# UWB_Conectores.net
KiCad netlist of a schematic drawn in Altium Designer
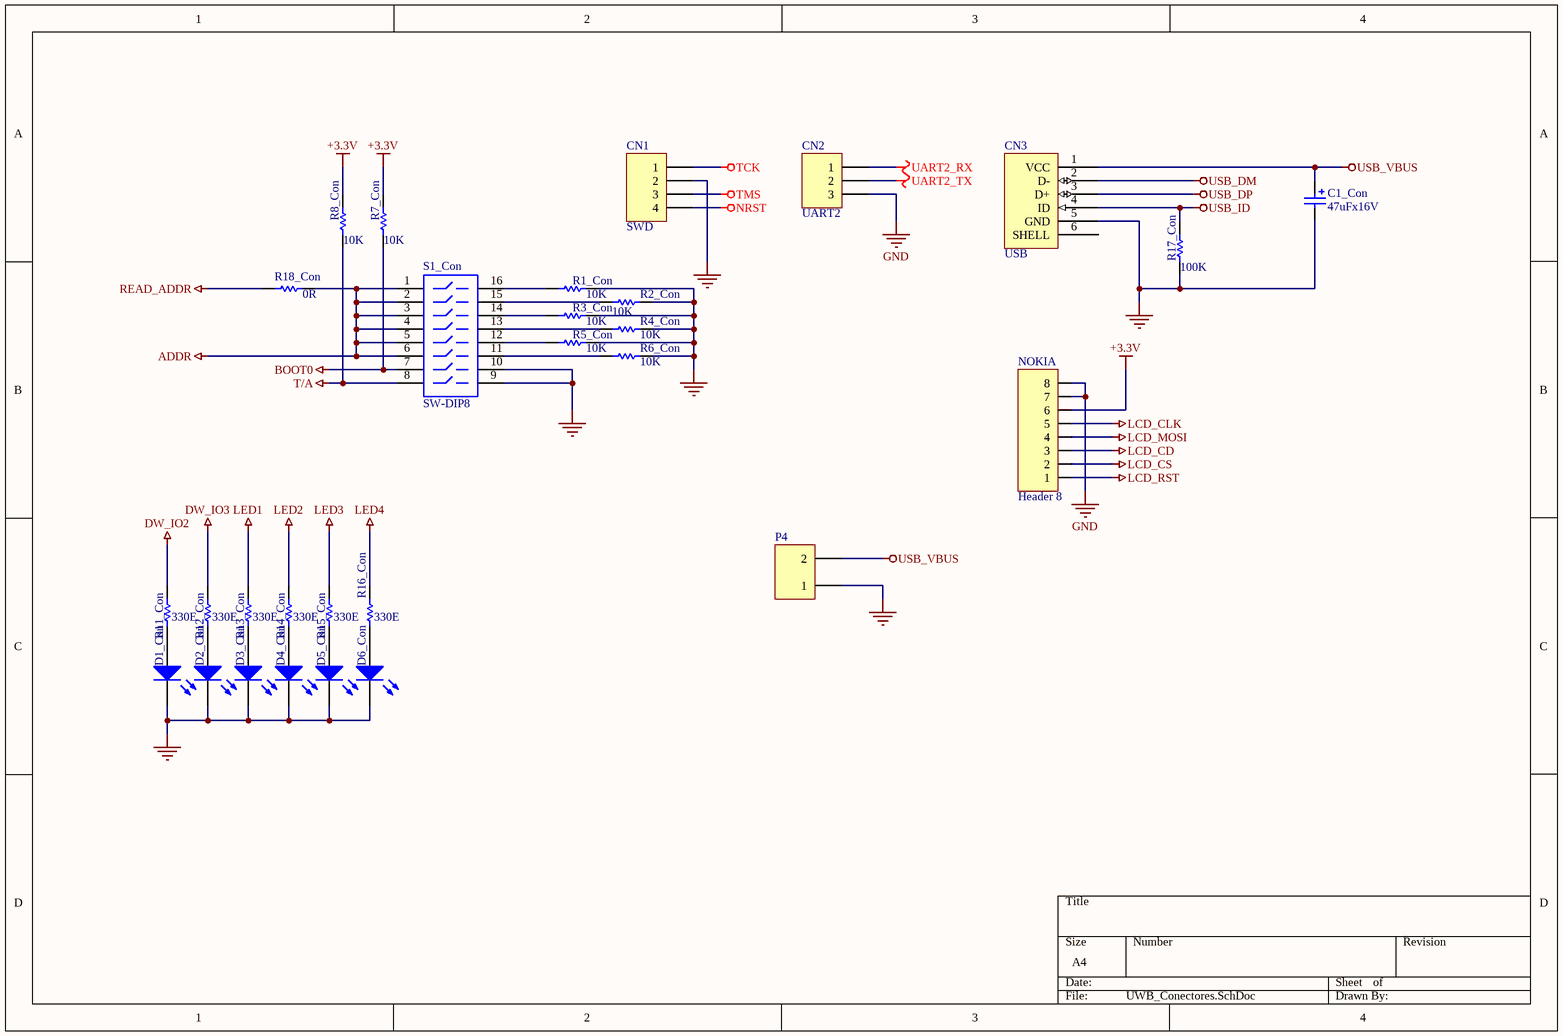
[diagram p0: UWB_Conectores.SchDoc]

(export (version "E")
  (design (tool "Eeschema 10.0.6"))
  (components
    (comp (ref "C1_Con")
      (value "47uFx16V")
      (footprint "Panasonic Size D (Dia. 6.3)")
      (description "Polarized Capacitor (Radial)")
      (fields (field (name "Comment") "Cap Pol1") (field (name "PUBLISHER") "Altium Limited"))
      (libsource (lib "Leo") (part "Cap Pol1"))
    )
    (comp (ref "CN1")
      (value "SWD")
      (footprint "Lib 01:HDR1X4 - SMALL")
      (description "Header, 4-Pin")
      (fields (field (name "PUBLISHER") "Altium Limited"))
      (libsource (lib "Miscellaneous Connectors") (part "Header 4"))
    )
    (comp (ref "CN2")
      (value "UART2")
      (footprint "HDR1X3")
      (description "Header, 3-Pin")
      (fields (field (name "PUBLISHER") "Altium Limited"))
      (libsource (lib "Miscellaneous Connectors") (part "Header 3"))
    )
    (comp (ref "CN3")
      (value "USB")
      (footprint "USB_Montaje")
      (description "USB-MINI-typeB connector")
      (libsource (lib "MCD_TOOLS") (part "USB-MINI-typeB connector"))
    )
    (comp (ref "D1_Con")
      (value "LED")
      (footprint "LED SMD 0805")
      (description "Typical INFRARED GaAs LED")
      (fields (field (name "PUBLISHER") "Altium Limited"))
      (libsource (lib "Leo") (part "LED"))
    )
    (comp (ref "D2_Con")
      (value "LED")
      (footprint "LED SMD 0805")
      (description "Typical INFRARED GaAs LED")
      (fields (field (name "PUBLISHER") "Altium Limited"))
      (libsource (lib "Leo") (part "LED"))
    )
    (comp (ref "D3_Con")
      (value "LED")
      (footprint "LED SMD 0805")
      (description "Typical INFRARED GaAs LED")
      (fields (field (name "PUBLISHER") "Altium Limited"))
      (libsource (lib "Leo") (part "LED"))
    )
    (comp (ref "D4_Con")
      (value "LED")
      (footprint "LED SMD 0805")
      (description "Typical INFRARED GaAs LED")
      (fields (field (name "PUBLISHER") "Altium Limited"))
      (libsource (lib "Leo") (part "LED"))
    )
    (comp (ref "D5_Con")
      (value "LED")
      (footprint "LED SMD 0805")
      (description "Typical INFRARED GaAs LED")
      (fields (field (name "PUBLISHER") "Altium Limited"))
      (libsource (lib "Leo") (part "LED"))
    )
    (comp (ref "D6_Con")
      (value "LED")
      (footprint "LED SMD 0805")
      (description "Typical INFRARED GaAs LED")
      (fields (field (name "PUBLISHER") "Altium Limited"))
      (libsource (lib "Leo") (part "LED"))
    )
    (comp (ref "NOKIA") (value "Header 8") (footprint "HDR1X8") (libsource (lib "Leo") (part "Header 8")))
    (comp (ref "P4")
      (value "Header 2")
      (footprint "HDR1X2")
      (description "Header, 2-Pin")
      (fields (field (name "PUBLISHER") "Altium Limited"))
      (libsource (lib "Leo") (part "Header 2"))
    )
    (comp (ref "R1_Con")
      (value "10K")
      (footprint "Chip_Resistor_M:RESC1608M")
      (description "Resistor")
      (fields (field (name "PUBLISHER") "Altium Limited"))
      (libsource (lib "Miscellaneous Devices") (part "res1"))
    )
    (comp (ref "R2_Con")
      (value "10K")
      (footprint "Chip_Resistor_M:RESC1608M")
      (description "Resistor")
      (fields (field (name "PUBLISHER") "Altium Limited"))
      (libsource (lib "Miscellaneous Devices") (part "res1"))
    )
    (comp (ref "R3_Con")
      (value "10K")
      (footprint "Chip_Resistor_M:RESC1608M")
      (description "Resistor")
      (fields (field (name "PUBLISHER") "Altium Limited"))
      (libsource (lib "Miscellaneous Devices") (part "res1"))
    )
    (comp (ref "R4_Con")
      (value "10K")
      (footprint "Chip_Resistor_M:RESC1608M")
      (description "Resistor")
      (fields (field (name "PUBLISHER") "Altium Limited"))
      (libsource (lib "Miscellaneous Devices") (part "res1"))
    )
    (comp (ref "R5_Con")
      (value "10K")
      (footprint "Chip_Resistor_M:RESC1608M")
      (description "Resistor")
      (fields (field (name "PUBLISHER") "Altium Limited"))
      (libsource (lib "Miscellaneous Devices") (part "res1"))
    )
    (comp (ref "R6_Con")
      (value "10K")
      (footprint "Chip_Resistor_M:RESC1608M")
      (description "Resistor")
      (fields (field (name "PUBLISHER") "Altium Limited"))
      (libsource (lib "Miscellaneous Devices") (part "res1"))
    )
    (comp (ref "R7_Con")
      (value "10K")
      (footprint "Chip_Resistor_M:RESC1608M")
      (description "Resistor")
      (fields (field (name "PUBLISHER") "Altium Limited"))
      (libsource (lib "Miscellaneous Devices") (part "res1"))
    )
    (comp (ref "R8_Con")
      (value "10K")
      (footprint "RESC1608N")
      (description "Resistor")
      (fields (field (name "PUBLISHER") "Altium Limited"))
      (libsource (lib "Miscellaneous Devices") (part "res1"))
    )
    (comp (ref "R11_Con")
      (value "330E")
      (footprint "RESC1608N")
      (description "Resistor")
      (fields (field (name "Comment") "Res1") (field (name "PUBLISHER") "Altium Limited"))
      (libsource (lib "Leo") (part "Res1"))
    )
    (comp (ref "R12_Con")
      (value "330E")
      (footprint "RESC1608N")
      (description "Resistor")
      (fields (field (name "Comment") "Res1") (field (name "PUBLISHER") "Altium Limited"))
      (libsource (lib "Leo") (part "Res1"))
    )
    (comp (ref "R13_Con")
      (value "330E")
      (footprint "RESC1608N")
      (description "Resistor")
      (fields (field (name "Comment") "Res1") (field (name "PUBLISHER") "Altium Limited"))
      (libsource (lib "Leo") (part "Res1"))
    )
    (comp (ref "R14_Con")
      (value "330E")
      (footprint "RESC1608N")
      (description "Resistor")
      (fields (field (name "Comment") "Res1") (field (name "PUBLISHER") "Altium Limited"))
      (libsource (lib "Leo") (part "Res1"))
    )
    (comp (ref "R15_Con")
      (value "330E")
      (footprint "RESC1608N")
      (description "Resistor")
      (fields (field (name "Comment") "Res1") (field (name "PUBLISHER") "Altium Limited"))
      (libsource (lib "Leo") (part "Res1"))
    )
    (comp (ref "R16_Con")
      (value "330E")
      (footprint "RESC1608N")
      (description "Resistor")
      (fields (field (name "Comment") "Res1") (field (name "PUBLISHER") "Altium Limited"))
      (libsource (lib "Leo") (part "Res1"))
    )
    (comp (ref "R17_Con")
      (value "100K")
      (footprint "Chip_Resistor_M:RESC1608M")
      (description "Resistor")
      (fields (field (name "Comment") "10K") (field (name "PUBLISHER") "Altium Limited"))
      (libsource (lib "Miscellaneous Devices") (part "res1"))
    )
    (comp (ref "R18_Con")
      (value "0R")
      (footprint "Chip_Resistor_M:RESC1608M")
      (description "Resistor")
      (fields (field (name "Comment") "10K") (field (name "PUBLISHER") "Altium Limited"))
      (libsource (lib "Miscellaneous Devices") (part "res1"))
    )
    (comp (ref "S1_Con")
      (value "SW-DIP8")
      (footprint "DIP-16-KEY")
      (description "4009 Series DIP Switch, Raised actuator")
      (fields (field (name "PUBLISHER") "Altium Limited"))
      (libsource (lib "Miscellaneous Devices") (part "SW-DIP8"))
    )
  )
  (nets
    (net (code "1") (name "+3.3V") (class "Default")
      (node (ref "NOKIA") (pin "6") (pinfunction "6_6") (pintype "passive"))
      (node (ref "R7_Con") (pin "1") (pinfunction "1_1") (pintype "passive"))
      (node (ref "R8_Con") (pin "1") (pinfunction "1_1") (pintype "passive"))
    )
    (net (code "2") (name "ADDR") (class "Default")
      (node (ref "R18_Con") (pin "2") (pinfunction "2_2") (pintype "passive"))
      (node (ref "S1_Con") (pin "1") (pinfunction "1_1") (pintype "passive"))
      (node (ref "S1_Con") (pin "2") (pinfunction "2_2") (pintype "passive"))
      (node (ref "S1_Con") (pin "3") (pinfunction "3_3") (pintype "passive"))
      (node (ref "S1_Con") (pin "4") (pinfunction "4_4") (pintype "passive"))
      (node (ref "S1_Con") (pin "5") (pinfunction "5_5") (pintype "passive"))
      (node (ref "S1_Con") (pin "6") (pinfunction "6_6") (pintype "passive"))
    )
    (net (code "3") (name "BOOT0") (class "Default")
      (node (ref "R7_Con") (pin "2") (pinfunction "2_2") (pintype "passive"))
      (node (ref "S1_Con") (pin "7") (pinfunction "7_7") (pintype "passive"))
    )
    (net (code "4") (name "DW_IO2") (class "Default")
      (node (ref "R11_Con") (pin "2") (pinfunction "2_2") (pintype "passive"))
    )
    (net (code "5") (name "DW_IO3") (class "Default")
      (node (ref "R12_Con") (pin "2") (pinfunction "2_2") (pintype "passive"))
    )
    (net (code "6") (name "GND") (class "Default")
      (node (ref "C1_Con") (pin "2") (pinfunction "2_2") (pintype "passive"))
      (node (ref "CN1") (pin "2") (pinfunction "2_2") (pintype "passive"))
      (node (ref "CN2") (pin "3") (pinfunction "3_3") (pintype "passive"))
      (node (ref "CN3") (pin "5") (pinfunction "GND_5") (pintype "power_in"))
      (node (ref "D1_Con") (pin "K") (pinfunction "K_K") (pintype "passive"))
      (node (ref "D2_Con") (pin "K") (pinfunction "K_K") (pintype "passive"))
      (node (ref "D3_Con") (pin "K") (pinfunction "K_K") (pintype "passive"))
      (node (ref "D4_Con") (pin "K") (pinfunction "K_K") (pintype "passive"))
      (node (ref "D5_Con") (pin "K") (pinfunction "K_K") (pintype "passive"))
      (node (ref "D6_Con") (pin "K") (pinfunction "K_K") (pintype "passive"))
      (node (ref "NOKIA") (pin "7") (pinfunction "7_7") (pintype "passive"))
      (node (ref "NOKIA") (pin "8") (pinfunction "8_8") (pintype "passive"))
      (node (ref "P4") (pin "1") (pinfunction "1_1") (pintype "passive"))
      (node (ref "R17_Con") (pin "2") (pinfunction "2_2") (pintype "passive"))
      (node (ref "R1_Con") (pin "2") (pinfunction "2_2") (pintype "passive"))
      (node (ref "R2_Con") (pin "1") (pinfunction "1_1") (pintype "passive"))
      (node (ref "R3_Con") (pin "1") (pinfunction "1_1") (pintype "passive"))
      (node (ref "R4_Con") (pin "1") (pinfunction "1_1") (pintype "passive"))
      (node (ref "R5_Con") (pin "1") (pinfunction "1_1") (pintype "passive"))
      (node (ref "R6_Con") (pin "1") (pinfunction "1_1") (pintype "passive"))
      (node (ref "S1_Con") (pin "10") (pinfunction "10_10") (pintype "passive"))
      (node (ref "S1_Con") (pin "9") (pinfunction "9_9") (pintype "passive"))
    )
    (net (code "7") (name "LCD_CD") (class "Default")
      (node (ref "NOKIA") (pin "3") (pinfunction "3_3") (pintype "passive"))
    )
    (net (code "8") (name "LCD_CLK") (class "Default")
      (node (ref "NOKIA") (pin "5") (pinfunction "5_5") (pintype "passive"))
    )
    (net (code "9") (name "LCD_CS") (class "Default")
      (node (ref "NOKIA") (pin "2") (pinfunction "2_2") (pintype "passive"))
    )
    (net (code "10") (name "LCD_MOSI") (class "Default")
      (node (ref "NOKIA") (pin "4") (pinfunction "4_4") (pintype "passive"))
    )
    (net (code "11") (name "LCD_RST") (class "Default")
      (node (ref "NOKIA") (pin "1") (pinfunction "1_1") (pintype "passive"))
    )
    (net (code "12") (name "LED1") (class "Default")
      (node (ref "R13_Con") (pin "2") (pinfunction "2_2") (pintype "passive"))
    )
    (net (code "13") (name "LED2") (class "Default")
      (node (ref "R14_Con") (pin "2") (pinfunction "2_2") (pintype "passive"))
    )
    (net (code "14") (name "LED3") (class "Default")
      (node (ref "R15_Con") (pin "2") (pinfunction "2_2") (pintype "passive"))
    )
    (net (code "15") (name "LED4") (class "Default")
      (node (ref "R16_Con") (pin "2") (pinfunction "2_2") (pintype "passive"))
    )
    (net (code "16") (name "NRST") (class "Default")
      (node (ref "CN1") (pin "4") (pinfunction "4_4") (pintype "passive"))
    )
    (net (code "17") (name "Net-(D1_Con-PadA)") (class "Default")
      (node (ref "D1_Con") (pin "A") (pinfunction "A_A") (pintype "passive"))
      (node (ref "R11_Con") (pin "1") (pinfunction "1_1") (pintype "passive"))
    )
    (net (code "18") (name "Net-(D2_Con-PadA)") (class "Default")
      (node (ref "D2_Con") (pin "A") (pinfunction "A_A") (pintype "passive"))
      (node (ref "R12_Con") (pin "1") (pinfunction "1_1") (pintype "passive"))
    )
    (net (code "19") (name "Net-(D3_Con-PadA)") (class "Default")
      (node (ref "D3_Con") (pin "A") (pinfunction "A_A") (pintype "passive"))
      (node (ref "R13_Con") (pin "1") (pinfunction "1_1") (pintype "passive"))
    )
    (net (code "20") (name "Net-(D4_Con-PadA)") (class "Default")
      (node (ref "D4_Con") (pin "A") (pinfunction "A_A") (pintype "passive"))
      (node (ref "R14_Con") (pin "1") (pinfunction "1_1") (pintype "passive"))
    )
    (net (code "21") (name "Net-(D5_Con-PadA)") (class "Default")
      (node (ref "D5_Con") (pin "A") (pinfunction "A_A") (pintype "passive"))
      (node (ref "R15_Con") (pin "1") (pinfunction "1_1") (pintype "passive"))
    )
    (net (code "22") (name "Net-(D6_Con-PadA)") (class "Default")
      (node (ref "D6_Con") (pin "A") (pinfunction "A_A") (pintype "passive"))
      (node (ref "R16_Con") (pin "1") (pinfunction "1_1") (pintype "passive"))
    )
    (net (code "23") (name "Net-(R1_Con-Pad1)") (class "Default")
      (node (ref "R1_Con") (pin "1") (pinfunction "1_1") (pintype "passive"))
      (node (ref "S1_Con") (pin "16") (pinfunction "16_16") (pintype "passive"))
    )
    (net (code "24") (name "Net-(R2_Con-Pad2)") (class "Default")
      (node (ref "R2_Con") (pin "2") (pinfunction "2_2") (pintype "passive"))
      (node (ref "S1_Con") (pin "15") (pinfunction "15_15") (pintype "passive"))
    )
    (net (code "25") (name "Net-(R3_Con-Pad2)") (class "Default")
      (node (ref "R3_Con") (pin "2") (pinfunction "2_2") (pintype "passive"))
      (node (ref "S1_Con") (pin "14") (pinfunction "14_14") (pintype "passive"))
    )
    (net (code "26") (name "Net-(R4_Con-Pad2)") (class "Default")
      (node (ref "R4_Con") (pin "2") (pinfunction "2_2") (pintype "passive"))
      (node (ref "S1_Con") (pin "13") (pinfunction "13_13") (pintype "passive"))
    )
    (net (code "27") (name "Net-(R5_Con-Pad2)") (class "Default")
      (node (ref "R5_Con") (pin "2") (pinfunction "2_2") (pintype "passive"))
      (node (ref "S1_Con") (pin "12") (pinfunction "12_12") (pintype "passive"))
    )
    (net (code "28") (name "Net-(R6_Con-Pad2)") (class "Default")
      (node (ref "R6_Con") (pin "2") (pinfunction "2_2") (pintype "passive"))
      (node (ref "S1_Con") (pin "11") (pinfunction "11_11") (pintype "passive"))
    )
    (net (code "29") (name "READ_ADDR") (class "Default")
      (node (ref "R18_Con") (pin "1") (pinfunction "1_1") (pintype "passive"))
    )
    (net (code "30") (name "TCK") (class "Default")
      (node (ref "CN1") (pin "1") (pinfunction "1_1") (pintype "passive"))
    )
    (net (code "31") (name "TMS") (class "Default")
      (node (ref "CN1") (pin "3") (pinfunction "3_3") (pintype "passive"))
    )
    (net (code "32") (name "T{slash}A") (class "Default")
      (node (ref "R8_Con") (pin "2") (pinfunction "2_2") (pintype "passive"))
      (node (ref "S1_Con") (pin "8") (pinfunction "8_8") (pintype "passive"))
    )
    (net (code "33") (name "UART2_RX") (class "Default")
      (node (ref "CN2") (pin "1") (pinfunction "1_1") (pintype "passive"))
    )
    (net (code "34") (name "UART2_TX") (class "Default")
      (node (ref "CN2") (pin "2") (pinfunction "2_2") (pintype "passive"))
    )
    (net (code "35") (name "USB_DM") (class "Default")
      (node (ref "CN3") (pin "2") (pinfunction "D-_2") (pintype "bidirectional"))
    )
    (net (code "36") (name "USB_DP") (class "Default")
      (node (ref "CN3") (pin "3") (pinfunction "D+_3") (pintype "bidirectional"))
    )
    (net (code "37") (name "USB_ID") (class "Default")
      (node (ref "CN3") (pin "4") (pinfunction "ID_4") (pintype "input"))
      (node (ref "R17_Con") (pin "1") (pinfunction "1_1") (pintype "passive"))
    )
    (net (code "38") (name "USB_VBUS") (class "Default")
      (node (ref "C1_Con") (pin "1") (pinfunction "1_1") (pintype "passive"))
      (node (ref "CN3") (pin "1") (pinfunction "VCC_1") (pintype "power_in"))
      (node (ref "P4") (pin "2") (pinfunction "2_2") (pintype "passive"))
    )
    (net (code "39") (name "unconnected-(CN3-SHELL-Pad6)") (class "Default")
      (node (ref "CN3") (pin "6") (pinfunction "SHELL_6") (pintype "power_in"))
    )
  )
)
